# ANT.net
KiCad netlist of a schematic drawn in Altium Designer
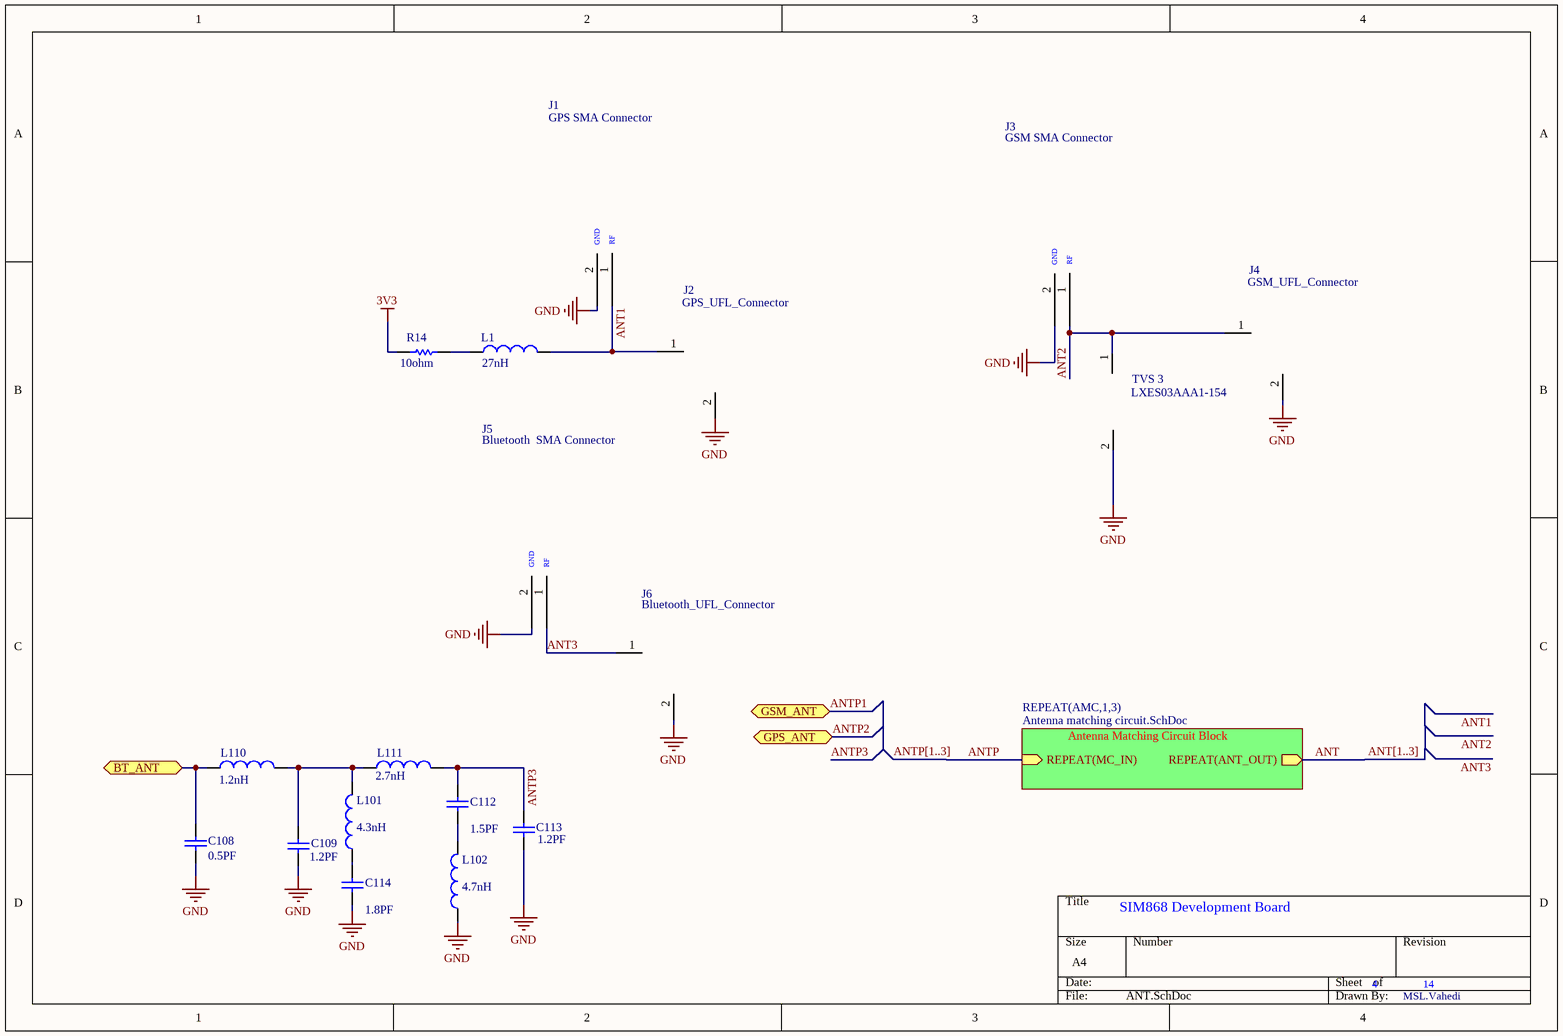
[diagram p0: ANT.SchDoc]

(export (version "E")
  (design (tool "Eeschema 10.0.6"))
  (components
    (comp (ref "C108")
      (value "0.5PF")
      (footprint "RAD-0.3")
      (description "Capacitor")
      (fields (field (name "PUBLISHER") "Altium Limited"))
      (libsource (lib "Miscellaneous Devices") (part "Cap"))
    )
    (comp (ref "C109")
      (value "1.2PF")
      (footprint "RAD-0.3")
      (description "Capacitor")
      (fields (field (name "PUBLISHER") "Altium Limited"))
      (libsource (lib "Miscellaneous Devices") (part "Cap"))
    )
    (comp (ref "C112")
      (value "1.5PF")
      (footprint "RAD-0.3")
      (description "Capacitor")
      (fields (field (name "PUBLISHER") "Altium Limited"))
      (libsource (lib "Miscellaneous Devices") (part "Cap"))
    )
    (comp (ref "C113")
      (value "1.2PF")
      (footprint "RAD-0.3")
      (description "Capacitor")
      (fields (field (name "PUBLISHER") "Altium Limited"))
      (libsource (lib "Miscellaneous Devices") (part "Cap"))
    )
    (comp (ref "C114")
      (value "1.8PF")
      (footprint "RAD-0.3")
      (description "Capacitor")
      (fields (field (name "PUBLISHER") "Altium Limited"))
      (libsource (lib "Miscellaneous Devices") (part "Cap"))
    )
    (comp (ref "J1")
      (value "GPS SMA Connector")
      (footprint "SMA right Angle")
      (libsource (lib "SMA  ") (part "SMA Connector"))
    )
    (comp (ref "J2")
      (value "GPS_UFL_Connector")
      (footprint "UFL_Connector")
      (libsource (lib "Schlib2") (part "UFL"))
    )
    (comp (ref "J3")
      (value "GSM SMA Connector")
      (footprint "SMA right Angle")
      (libsource (lib "SMA  ") (part "SMA Connector"))
    )
    (comp (ref "J4")
      (value "GSM_UFL_Connector")
      (footprint "UFL_Connector")
      (libsource (lib "Schlib2") (part "UFL"))
    )
    (comp (ref "J5")
      (value "Bluetooth  SMA Connector")
      (footprint "SMA right Angle")
      (libsource (lib "SMA  ") (part "SMA Connector"))
    )
    (comp (ref "J6")
      (value "Bluetooth_UFL_Connector")
      (footprint "UFL_Connector")
      (libsource (lib "Schlib2") (part "UFL"))
    )
    (comp (ref "L1")
      (value "27nH")
      (footprint "INDC1608L")
      (description "Inductor")
      (fields (field (name "PUBLISHER") "Altium Limited"))
      (libsource (lib "Miscellaneous Devices") (part "Inductor"))
    )
    (comp (ref "L101")
      (value "4.3nH")
      (footprint "0402-A")
      (description "Inductor")
      (fields (field (name "PUBLISHER") "Altium Limited"))
      (libsource (lib "Miscellaneous Devices") (part "Inductor"))
    )
    (comp (ref "L102")
      (value "4.7nH")
      (footprint "0402-A")
      (description "Inductor")
      (fields (field (name "PUBLISHER") "Altium Limited"))
      (libsource (lib "Miscellaneous Devices") (part "Inductor"))
    )
    (comp (ref "L110")
      (value "1.2nH")
      (footprint "0402-A")
      (description "Inductor")
      (fields (field (name "PUBLISHER") "Altium Limited"))
      (libsource (lib "Miscellaneous Devices") (part "Inductor"))
    )
    (comp (ref "L111")
      (value "2.7nH")
      (footprint "0402-A")
      (description "Inductor")
      (fields (field (name "PUBLISHER") "Altium Limited"))
      (libsource (lib "Miscellaneous Devices") (part "Inductor"))
    )
    (comp (ref "R14")
      (value "10ohm")
      (footprint "RES0805")
      (description "Resistor")
      (fields (field (name "PUBLISHER") "Altium Limited"))
      (libsource (lib "Miscellaneous Devices") (part "Res1"))
    )
    (comp (ref "TVS 3")
      (value "LXES03AAA1-154")
      (footprint "*FB_BLM18PG121SN1D")
      (description "Recommended vendor  MURATA LXE03AAA1-154 Ζ MURATA LXES015AAA1-154")
      (libsource (lib "SMA  ") (part "TVS"))
    )
  )
  (nets
    (net (code "2") (name "/ANT1") (class "Default")
      (node (ref "J1") (pin "1") (pinfunction "RF_1") (pintype "passive"))
      (node (ref "J2") (pin "1") (pintype "passive"))
      (node (ref "L1") (pin "2") (pinfunction "2_2") (pintype "passive"))
    )
    (net (code "3") (name "/ANT2") (class "Default")
      (node (ref "J3") (pin "1") (pinfunction "RF_1") (pintype "passive"))
      (node (ref "J4") (pin "1") (pintype "passive"))
      (node (ref "TVS 3") (pin "1") (pintype "passive"))
    )
    (net (code "4") (name "/ANT3") (class "Default")
      (node (ref "J5") (pin "1") (pinfunction "RF_1") (pintype "passive"))
      (node (ref "J6") (pin "1") (pintype "passive"))
    )
    (net (code "8") (name "/ANTP3") (class "Default")
      (node (ref "C112") (pin "2") (pinfunction "2_2") (pintype "passive"))
      (node (ref "C113") (pin "2") (pinfunction "2_2") (pintype "passive"))
      (node (ref "L111") (pin "2") (pinfunction "2_2") (pintype "passive"))
    )
    (net (code "11") (name "/BT_ANT") (class "Default")
      (node (ref "C108") (pin "2") (pinfunction "2_2") (pintype "passive"))
      (node (ref "L110") (pin "1") (pinfunction "1_1") (pintype "passive"))
    )
    (net (code "12") (name "3V3") (class "Default")
      (node (ref "R14") (pin "1") (pinfunction "1_1") (pintype "passive"))
    )
    (net (code "13") (name "GND") (class "Default")
      (node (ref "C108") (pin "1") (pinfunction "1_1") (pintype "passive"))
      (node (ref "C109") (pin "1") (pinfunction "1_1") (pintype "passive"))
      (node (ref "C113") (pin "1") (pinfunction "1_1") (pintype "passive"))
      (node (ref "C114") (pin "1") (pinfunction "1_1") (pintype "passive"))
      (node (ref "J1") (pin "2") (pinfunction "GND_2") (pintype "passive"))
      (node (ref "J2") (pin "2") (pintype "passive"))
      (node (ref "J3") (pin "2") (pinfunction "GND_2") (pintype "passive"))
      (node (ref "J4") (pin "2") (pintype "passive"))
      (node (ref "J5") (pin "2") (pinfunction "GND_2") (pintype "passive"))
      (node (ref "J6") (pin "2") (pintype "passive"))
      (node (ref "L102") (pin "1") (pinfunction "1_1") (pintype "passive"))
      (node (ref "TVS 3") (pin "2") (pintype "passive"))
    )
    (net (code "14") (name "Net-(C109-Pad2)") (class "Default")
      (node (ref "C109") (pin "2") (pinfunction "2_2") (pintype "passive"))
      (node (ref "L101") (pin "2") (pinfunction "2_2") (pintype "passive"))
      (node (ref "L110") (pin "2") (pinfunction "2_2") (pintype "passive"))
      (node (ref "L111") (pin "1") (pinfunction "1_1") (pintype "passive"))
    )
    (net (code "15") (name "Net-(C112-Pad1)") (class "Default")
      (node (ref "C112") (pin "1") (pinfunction "1_1") (pintype "passive"))
      (node (ref "L102") (pin "2") (pinfunction "2_2") (pintype "passive"))
    )
    (net (code "16") (name "Net-(C114-Pad2)") (class "Default")
      (node (ref "C114") (pin "2") (pinfunction "2_2") (pintype "passive"))
      (node (ref "L101") (pin "1") (pinfunction "1_1") (pintype "passive"))
    )
    (net (code "17") (name "Net-(L1-Pad1)") (class "Default")
      (node (ref "L1") (pin "1") (pinfunction "1_1") (pintype "passive"))
      (node (ref "R14") (pin "2") (pinfunction "2_2") (pintype "passive"))
    )
  )
)
